# Nichome_with_Relay.net
KiCad netlist of a schematic drawn in EAGLE
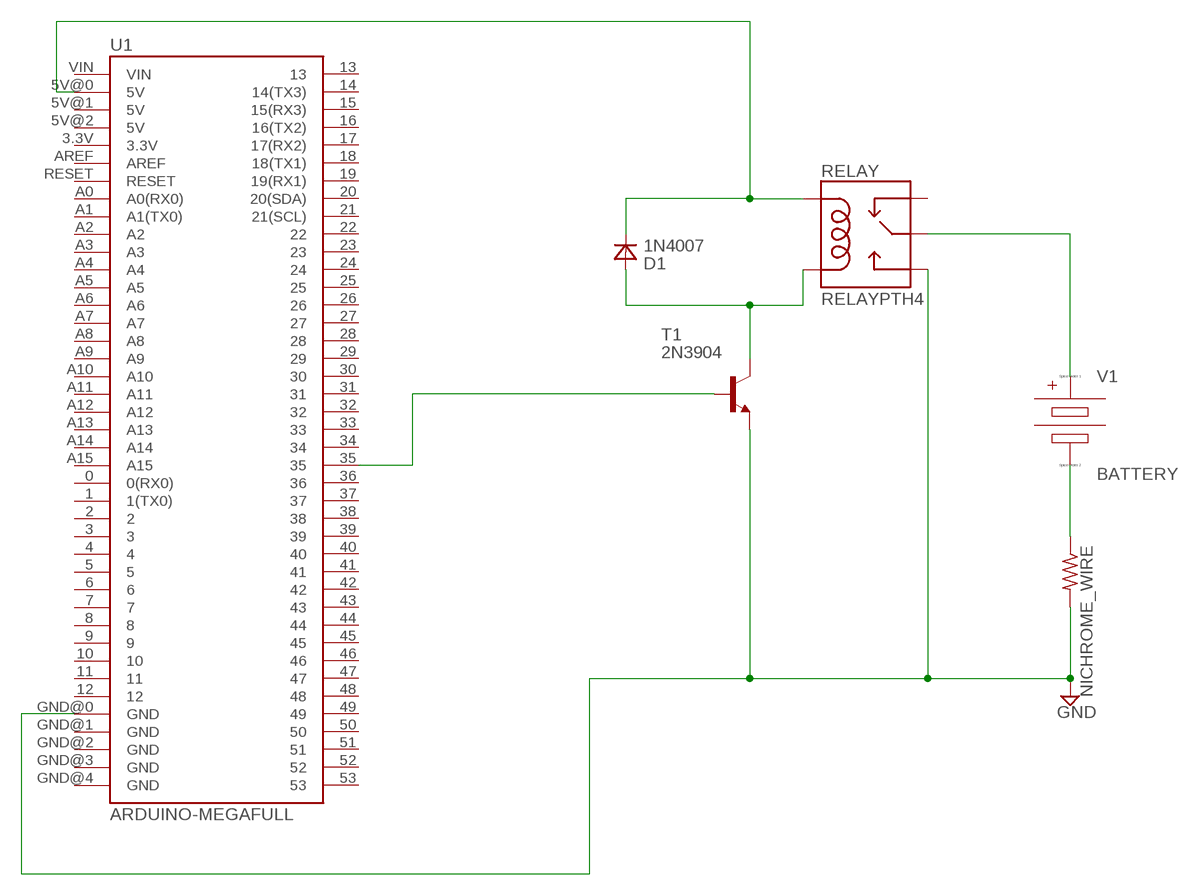
[diagram p0: schematic, sheet 1]

(export (version "E")
  (design (tool "Eeschema 10.0.6"))
  (components
    (comp (ref "D1")
      (value "1N4007")
      (footprint "eagle-import:DIODE")
      (libsource (lib "eagle-import") (part "DIODE"))
    )
    (comp (ref "NICHROME_WIRE")
      (value "FLIPFLOP-RES")
      (footprint "eagle-import:0805-THM")
      (libsource (lib "eagle-import") (part "FLIPFLOP-RES"))
    )
    (comp (ref "RELAY")
      (value "RELAYPTH4")
      (footprint "eagle-import:RELAY-JZC")
      (libsource (lib "eagle-import") (part "RELAYPTH4"))
    )
    (comp (ref "T1")
      (value "2N3904")
      (footprint "eagle-import:TO92")
      (libsource (lib "eagle-import") (part "2N3904"))
    )
    (comp (ref "U1")
      (value "ARDUINO-MEGAFULL")
      (footprint "eagle-import:ARDUINO_MEGA")
      (libsource (lib "eagle-import") (part "ARDUINO-MEGAFULL"))
    )
    (comp (ref "V1")
      (value "BATTERY")
      (footprint "eagle-import:3V60R")
      (libsource (lib "eagle-import") (part "BATTERY"))
    )
  )
  (nets
    (net (code "1") (name "GND") (class "Default")
      (node (ref "NICHROME_WIRE") (pin "2") (pinfunction "2_2") (pintype "passive"))
      (node (ref "RELAY") (pin "3") (pinfunction "NO_3") (pintype "bidirectional"))
      (node (ref "T1") (pin "3") (pinfunction "E_3") (pintype "passive"))
      (node (ref "U1") (pin "GND@0") (pinfunction "GND_GND@0") (pintype "bidirectional"))
    )
    (net (code "2") (name "Net-(NICHROME_WIRE-Pad1)") (class "Default")
      (node (ref "NICHROME_WIRE") (pin "1") (pinfunction "1_1") (pintype "passive"))
      (node (ref "V1") (pin "-") (pinfunction "-_-") (pintype "passive"))
    )
    (net (code "3") (name "Net-(RELAY-COIL1)") (class "Default")
      (node (ref "D1") (pin "A") (pinfunction "A_A") (pintype "input"))
      (node (ref "RELAY") (pin "5") (pinfunction "COIL1_5") (pintype "bidirectional"))
      (node (ref "U1") (pin "5V@0") (pinfunction "5V_5V@0") (pintype "bidirectional"))
    )
    (net (code "4") (name "Net-(RELAY-COIL2)") (class "Default")
      (node (ref "D1") (pin "C") (pinfunction "C_C") (pintype "input"))
      (node (ref "RELAY") (pin "1") (pinfunction "COIL2_1") (pintype "bidirectional"))
      (node (ref "T1") (pin "1") (pinfunction "C_1") (pintype "passive"))
    )
    (net (code "5") (name "Net-(RELAY-MAIN)") (class "Default")
      (node (ref "RELAY") (pin "4") (pinfunction "MAIN_4") (pintype "bidirectional"))
      (node (ref "V1") (pin "+") (pinfunction "+_+") (pintype "passive"))
      (node (ref "V1") (pin "+@1") (pinfunction "+_+@1") (pintype "passive"))
    )
    (net (code "6") (name "Net-(T1-B)") (class "Default")
      (node (ref "T1") (pin "2") (pinfunction "B_2") (pintype "passive"))
      (node (ref "U1") (pin "35") (pinfunction "35_35") (pintype "bidirectional"))
    )
    (net (code "7") (name "unconnected-(RELAY-NC-Pad2)") (class "Default")
      (node (ref "RELAY") (pin "2") (pinfunction "NC_2") (pintype "bidirectional"))
    )
    (net (code "8") (name "unconnected-(U1-0(RX0)-Pad0)") (class "Default")
      (node (ref "U1") (pin "0") (pinfunction "0(RX0)_0") (pintype "bidirectional"))
    )
    (net (code "9") (name "unconnected-(U1-1(TX0)-Pad1)") (class "Default")
      (node (ref "U1") (pin "1") (pinfunction "1(TX0)_1") (pintype "bidirectional"))
    )
    (net (code "10") (name "unconnected-(U1-5V-Pad5V@1)") (class "Default")
      (node (ref "U1") (pin "5V@1") (pinfunction "5V_5V@1") (pintype "bidirectional"))
    )
    (net (code "11") (name "unconnected-(U1-5V-Pad5V@2)") (class "Default")
      (node (ref "U1") (pin "5V@2") (pinfunction "5V_5V@2") (pintype "bidirectional"))
    )
    (net (code "12") (name "unconnected-(U1-14(TX3)-Pad14)") (class "Default")
      (node (ref "U1") (pin "14") (pinfunction "14(TX3)_14") (pintype "bidirectional"))
    )
    (net (code "13") (name "unconnected-(U1-15(RX3)-Pad15)") (class "Default")
      (node (ref "U1") (pin "15") (pinfunction "15(RX3)_15") (pintype "bidirectional"))
    )
    (net (code "14") (name "unconnected-(U1-16(TX2)-Pad16)") (class "Default")
      (node (ref "U1") (pin "16") (pinfunction "16(TX2)_16") (pintype "bidirectional"))
    )
    (net (code "15") (name "unconnected-(U1-17(RX2)-Pad17)") (class "Default")
      (node (ref "U1") (pin "17") (pinfunction "17(RX2)_17") (pintype "bidirectional"))
    )
    (net (code "16") (name "unconnected-(U1-18(TX1)-Pad18)") (class "Default")
      (node (ref "U1") (pin "18") (pinfunction "18(TX1)_18") (pintype "bidirectional"))
    )
    (net (code "17") (name "unconnected-(U1-19(RX1)-Pad19)") (class "Default")
      (node (ref "U1") (pin "19") (pinfunction "19(RX1)_19") (pintype "bidirectional"))
    )
    (net (code "18") (name "unconnected-(U1-20(SDA)-Pad20)") (class "Default")
      (node (ref "U1") (pin "20") (pinfunction "20(SDA)_20") (pintype "bidirectional"))
    )
    (net (code "19") (name "unconnected-(U1-21(SCL)-Pad21)") (class "Default")
      (node (ref "U1") (pin "21") (pinfunction "21(SCL)_21") (pintype "bidirectional"))
    )
    (net (code "20") (name "unconnected-(U1-A0(RX0)-PadA0)") (class "Default")
      (node (ref "U1") (pin "A0") (pinfunction "A0(RX0)_A0") (pintype "bidirectional"))
    )
    (net (code "21") (name "unconnected-(U1-A1(TX0)-PadA1)") (class "Default")
      (node (ref "U1") (pin "A1") (pinfunction "A1(TX0)_A1") (pintype "bidirectional"))
    )
    (net (code "22") (name "unconnected-(U1-GND-PadGND@1)") (class "Default")
      (node (ref "U1") (pin "GND@1") (pinfunction "GND_GND@1") (pintype "bidirectional"))
    )
    (net (code "23") (name "unconnected-(U1-GND-PadGND@2)") (class "Default")
      (node (ref "U1") (pin "GND@2") (pinfunction "GND_GND@2") (pintype "bidirectional"))
    )
    (net (code "24") (name "unconnected-(U1-GND-PadGND@3)") (class "Default")
      (node (ref "U1") (pin "GND@3") (pinfunction "GND_GND@3") (pintype "bidirectional"))
    )
    (net (code "25") (name "unconnected-(U1-GND-PadGND@4)") (class "Default")
      (node (ref "U1") (pin "GND@4") (pinfunction "GND_GND@4") (pintype "bidirectional"))
    )
    (net (code "26") (name "unconnected-(U1-Pad2)") (class "Default")
      (node (ref "U1") (pin "2") (pinfunction "2_2") (pintype "bidirectional"))
    )
    (net (code "27") (name "unconnected-(U1-Pad3)") (class "Default")
      (node (ref "U1") (pin "3") (pinfunction "3_3") (pintype "bidirectional"))
    )
    (net (code "28") (name "unconnected-(U1-Pad3.3V)") (class "Default")
      (node (ref "U1") (pin "3.3V") (pinfunction "3.3V_3.3V") (pintype "bidirectional"))
    )
    (net (code "29") (name "unconnected-(U1-Pad4)") (class "Default")
      (node (ref "U1") (pin "4") (pinfunction "4_4") (pintype "bidirectional"))
    )
    (net (code "30") (name "unconnected-(U1-Pad5)") (class "Default")
      (node (ref "U1") (pin "5") (pinfunction "5_5") (pintype "bidirectional"))
    )
    (net (code "31") (name "unconnected-(U1-Pad6)") (class "Default")
      (node (ref "U1") (pin "6") (pinfunction "6_6") (pintype "bidirectional"))
    )
    (net (code "32") (name "unconnected-(U1-Pad7)") (class "Default")
      (node (ref "U1") (pin "7") (pinfunction "7_7") (pintype "bidirectional"))
    )
    (net (code "33") (name "unconnected-(U1-Pad8)") (class "Default")
      (node (ref "U1") (pin "8") (pinfunction "8_8") (pintype "bidirectional"))
    )
    (net (code "34") (name "unconnected-(U1-Pad9)") (class "Default")
      (node (ref "U1") (pin "9") (pinfunction "9_9") (pintype "bidirectional"))
    )
    (net (code "35") (name "unconnected-(U1-Pad10)") (class "Default")
      (node (ref "U1") (pin "10") (pinfunction "10_10") (pintype "bidirectional"))
    )
    (net (code "36") (name "unconnected-(U1-Pad11)") (class "Default")
      (node (ref "U1") (pin "11") (pinfunction "11_11") (pintype "bidirectional"))
    )
    (net (code "37") (name "unconnected-(U1-Pad12)") (class "Default")
      (node (ref "U1") (pin "12") (pinfunction "12_12") (pintype "bidirectional"))
    )
    (net (code "38") (name "unconnected-(U1-Pad13)") (class "Default")
      (node (ref "U1") (pin "13") (pinfunction "13_13") (pintype "bidirectional"))
    )
    (net (code "39") (name "unconnected-(U1-Pad22)") (class "Default")
      (node (ref "U1") (pin "22") (pinfunction "22_22") (pintype "bidirectional"))
    )
    (net (code "40") (name "unconnected-(U1-Pad23)") (class "Default")
      (node (ref "U1") (pin "23") (pinfunction "23_23") (pintype "bidirectional"))
    )
    (net (code "41") (name "unconnected-(U1-Pad24)") (class "Default")
      (node (ref "U1") (pin "24") (pinfunction "24_24") (pintype "bidirectional"))
    )
    (net (code "42") (name "unconnected-(U1-Pad25)") (class "Default")
      (node (ref "U1") (pin "25") (pinfunction "25_25") (pintype "bidirectional"))
    )
    (net (code "43") (name "unconnected-(U1-Pad26)") (class "Default")
      (node (ref "U1") (pin "26") (pinfunction "26_26") (pintype "bidirectional"))
    )
    (net (code "44") (name "unconnected-(U1-Pad27)") (class "Default")
      (node (ref "U1") (pin "27") (pinfunction "27_27") (pintype "bidirectional"))
    )
    (net (code "45") (name "unconnected-(U1-Pad28)") (class "Default")
      (node (ref "U1") (pin "28") (pinfunction "28_28") (pintype "bidirectional"))
    )
    (net (code "46") (name "unconnected-(U1-Pad29)") (class "Default")
      (node (ref "U1") (pin "29") (pinfunction "29_29") (pintype "bidirectional"))
    )
    (net (code "47") (name "unconnected-(U1-Pad30)") (class "Default")
      (node (ref "U1") (pin "30") (pinfunction "30_30") (pintype "bidirectional"))
    )
    (net (code "48") (name "unconnected-(U1-Pad31)") (class "Default")
      (node (ref "U1") (pin "31") (pinfunction "31_31") (pintype "bidirectional"))
    )
    (net (code "49") (name "unconnected-(U1-Pad32)") (class "Default")
      (node (ref "U1") (pin "32") (pinfunction "32_32") (pintype "bidirectional"))
    )
    (net (code "50") (name "unconnected-(U1-Pad33)") (class "Default")
      (node (ref "U1") (pin "33") (pinfunction "33_33") (pintype "bidirectional"))
    )
    (net (code "51") (name "unconnected-(U1-Pad34)") (class "Default")
      (node (ref "U1") (pin "34") (pinfunction "34_34") (pintype "bidirectional"))
    )
    (net (code "52") (name "unconnected-(U1-Pad36)") (class "Default")
      (node (ref "U1") (pin "36") (pinfunction "36_36") (pintype "bidirectional"))
    )
    (net (code "53") (name "unconnected-(U1-Pad37)") (class "Default")
      (node (ref "U1") (pin "37") (pinfunction "37_37") (pintype "bidirectional"))
    )
    (net (code "54") (name "unconnected-(U1-Pad38)") (class "Default")
      (node (ref "U1") (pin "38") (pinfunction "38_38") (pintype "bidirectional"))
    )
    (net (code "55") (name "unconnected-(U1-Pad39)") (class "Default")
      (node (ref "U1") (pin "39") (pinfunction "39_39") (pintype "bidirectional"))
    )
    (net (code "56") (name "unconnected-(U1-Pad40)") (class "Default")
      (node (ref "U1") (pin "40") (pinfunction "40_40") (pintype "bidirectional"))
    )
    (net (code "57") (name "unconnected-(U1-Pad41)") (class "Default")
      (node (ref "U1") (pin "41") (pinfunction "41_41") (pintype "bidirectional"))
    )
    (net (code "58") (name "unconnected-(U1-Pad42)") (class "Default")
      (node (ref "U1") (pin "42") (pinfunction "42_42") (pintype "bidirectional"))
    )
    (net (code "59") (name "unconnected-(U1-Pad43)") (class "Default")
      (node (ref "U1") (pin "43") (pinfunction "43_43") (pintype "bidirectional"))
    )
    (net (code "60") (name "unconnected-(U1-Pad44)") (class "Default")
      (node (ref "U1") (pin "44") (pinfunction "44_44") (pintype "bidirectional"))
    )
    (net (code "61") (name "unconnected-(U1-Pad45)") (class "Default")
      (node (ref "U1") (pin "45") (pinfunction "45_45") (pintype "bidirectional"))
    )
    (net (code "62") (name "unconnected-(U1-Pad46)") (class "Default")
      (node (ref "U1") (pin "46") (pinfunction "46_46") (pintype "bidirectional"))
    )
    (net (code "63") (name "unconnected-(U1-Pad47)") (class "Default")
      (node (ref "U1") (pin "47") (pinfunction "47_47") (pintype "bidirectional"))
    )
    (net (code "64") (name "unconnected-(U1-Pad48)") (class "Default")
      (node (ref "U1") (pin "48") (pinfunction "48_48") (pintype "bidirectional"))
    )
    (net (code "65") (name "unconnected-(U1-Pad49)") (class "Default")
      (node (ref "U1") (pin "49") (pinfunction "49_49") (pintype "bidirectional"))
    )
    (net (code "66") (name "unconnected-(U1-Pad50)") (class "Default")
      (node (ref "U1") (pin "50") (pinfunction "50_50") (pintype "bidirectional"))
    )
    (net (code "67") (name "unconnected-(U1-Pad51)") (class "Default")
      (node (ref "U1") (pin "51") (pinfunction "51_51") (pintype "bidirectional"))
    )
    (net (code "68") (name "unconnected-(U1-Pad52)") (class "Default")
      (node (ref "U1") (pin "52") (pinfunction "52_52") (pintype "bidirectional"))
    )
    (net (code "69") (name "unconnected-(U1-Pad53)") (class "Default")
      (node (ref "U1") (pin "53") (pinfunction "53_53") (pintype "bidirectional"))
    )
    (net (code "70") (name "unconnected-(U1-PadA2)") (class "Default")
      (node (ref "U1") (pin "A2") (pinfunction "A2_A2") (pintype "bidirectional"))
    )
    (net (code "71") (name "unconnected-(U1-PadA3)") (class "Default")
      (node (ref "U1") (pin "A3") (pinfunction "A3_A3") (pintype "bidirectional"))
    )
    (net (code "72") (name "unconnected-(U1-PadA4)") (class "Default")
      (node (ref "U1") (pin "A4") (pinfunction "A4_A4") (pintype "bidirectional"))
    )
    (net (code "73") (name "unconnected-(U1-PadA5)") (class "Default")
      (node (ref "U1") (pin "A5") (pinfunction "A5_A5") (pintype "bidirectional"))
    )
    (net (code "74") (name "unconnected-(U1-PadA6)") (class "Default")
      (node (ref "U1") (pin "A6") (pinfunction "A6_A6") (pintype "bidirectional"))
    )
    (net (code "75") (name "unconnected-(U1-PadA7)") (class "Default")
      (node (ref "U1") (pin "A7") (pinfunction "A7_A7") (pintype "bidirectional"))
    )
    (net (code "76") (name "unconnected-(U1-PadA8)") (class "Default")
      (node (ref "U1") (pin "A8") (pinfunction "A8_A8") (pintype "bidirectional"))
    )
    (net (code "77") (name "unconnected-(U1-PadA9)") (class "Default")
      (node (ref "U1") (pin "A9") (pinfunction "A9_A9") (pintype "bidirectional"))
    )
    (net (code "78") (name "unconnected-(U1-PadA10)") (class "Default")
      (node (ref "U1") (pin "A10") (pinfunction "A10_A10") (pintype "bidirectional"))
    )
    (net (code "79") (name "unconnected-(U1-PadA11)") (class "Default")
      (node (ref "U1") (pin "A11") (pinfunction "A11_A11") (pintype "bidirectional"))
    )
    (net (code "80") (name "unconnected-(U1-PadA12)") (class "Default")
      (node (ref "U1") (pin "A12") (pinfunction "A12_A12") (pintype "bidirectional"))
    )
    (net (code "81") (name "unconnected-(U1-PadA13)") (class "Default")
      (node (ref "U1") (pin "A13") (pinfunction "A13_A13") (pintype "bidirectional"))
    )
    (net (code "82") (name "unconnected-(U1-PadA14)") (class "Default")
      (node (ref "U1") (pin "A14") (pinfunction "A14_A14") (pintype "bidirectional"))
    )
    (net (code "83") (name "unconnected-(U1-PadA15)") (class "Default")
      (node (ref "U1") (pin "A15") (pinfunction "A15_A15") (pintype "bidirectional"))
    )
    (net (code "84") (name "unconnected-(U1-PadAREF)") (class "Default")
      (node (ref "U1") (pin "AREF") (pinfunction "AREF_AREF") (pintype "bidirectional"))
    )
    (net (code "85") (name "unconnected-(U1-PadRESET)") (class "Default")
      (node (ref "U1") (pin "RESET") (pinfunction "RESET_RESET") (pintype "bidirectional"))
    )
    (net (code "86") (name "unconnected-(U1-PadVIN)") (class "Default")
      (node (ref "U1") (pin "VIN") (pinfunction "VIN_VIN") (pintype "bidirectional"))
    )
  )
)
